# cirq_lcd.net
KiCad netlist of a schematic drawn in Altium Designer
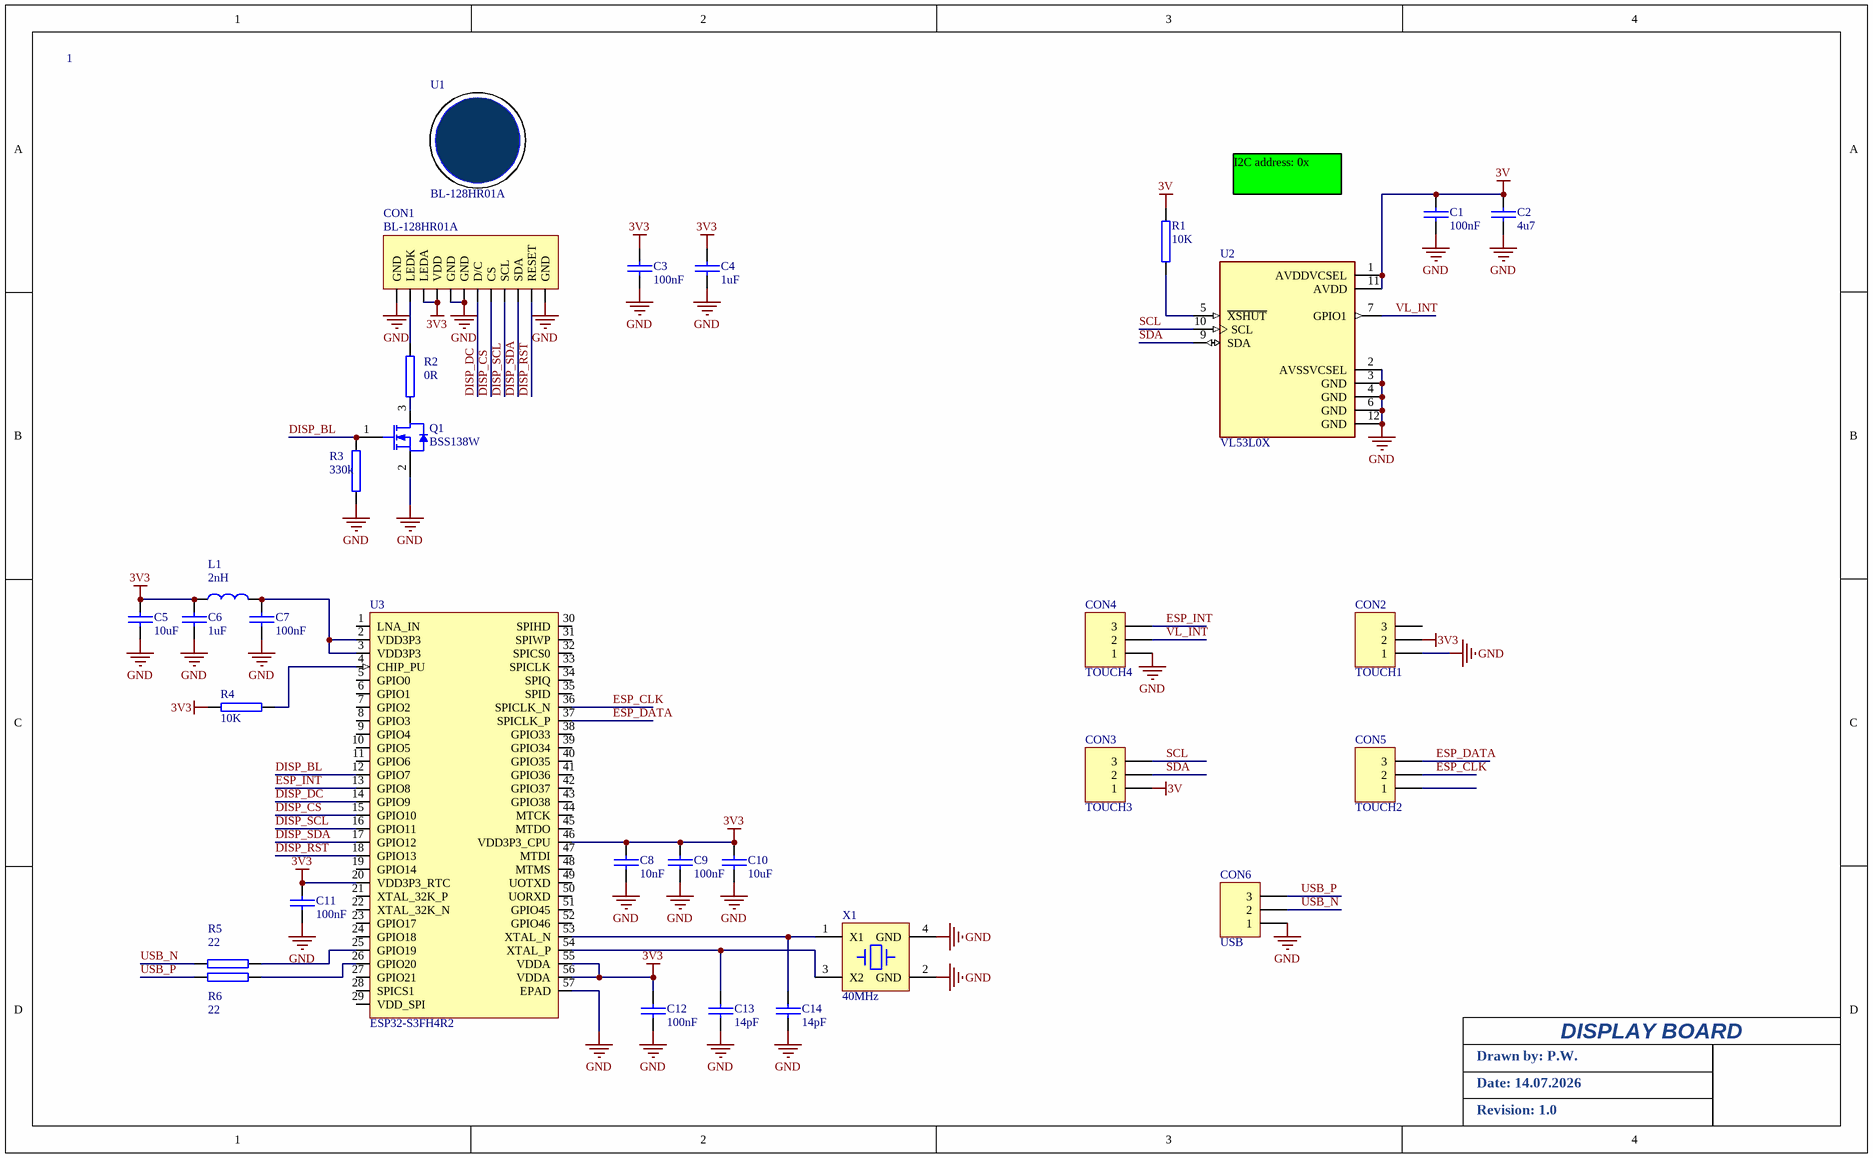
[diagram p0: cirq_lcd.SchDoc]

(export (version "E")
  (design (tool "Eeschema 10.0.6"))
  (components
    (comp (ref "1") (value "~") (footprint "NEWLOGO2") (libsource (lib "LIB_PW") (part "LOGO")))
    (comp (ref "C1")
      (value "100nF")
      (footprint "C0603L")
      (description "Capacitor")
      (libsource (lib "LIB_PW") (part "CAP"))
    )
    (comp (ref "C2")
      (value "4u7")
      (footprint "C0603L")
      (description "Capacitor")
      (libsource (lib "LIB_PW") (part "CAP"))
    )
    (comp (ref "C3")
      (value "100nF")
      (footprint "C0603L")
      (description "Capacitor")
      (libsource (lib "LIB_PW") (part "CAP"))
    )
    (comp (ref "C4")
      (value "1uF")
      (footprint "C0603L")
      (description "Capacitor")
      (libsource (lib "LIB_PW") (part "CAP"))
    )
    (comp (ref "C5")
      (value "10uF")
      (footprint "C0603L")
      (description "Capacitor")
      (libsource (lib "LIB_PW") (part "CAP"))
    )
    (comp (ref "C6")
      (value "1uF")
      (footprint "C0603L")
      (description "Capacitor")
      (libsource (lib "LIB_PW") (part "CAP"))
    )
    (comp (ref "C7")
      (value "100nF")
      (footprint "C0603L")
      (description "Capacitor")
      (libsource (lib "LIB_PW") (part "CAP"))
    )
    (comp (ref "C8")
      (value "10nF")
      (footprint "C0603L")
      (description "Capacitor")
      (libsource (lib "LIB_PW") (part "CAP"))
    )
    (comp (ref "C9")
      (value "100nF")
      (footprint "C0603L")
      (description "Capacitor")
      (libsource (lib "LIB_PW") (part "CAP"))
    )
    (comp (ref "C10")
      (value "10uF")
      (footprint "C0603L")
      (description "Capacitor")
      (libsource (lib "LIB_PW") (part "CAP"))
    )
    (comp (ref "C11")
      (value "100nF")
      (footprint "C0603L")
      (description "Capacitor")
      (libsource (lib "LIB_PW") (part "CAP"))
    )
    (comp (ref "C12")
      (value "100nF")
      (footprint "C0603L")
      (description "Capacitor")
      (libsource (lib "LIB_PW") (part "CAP"))
    )
    (comp (ref "C13")
      (value "14pF")
      (footprint "C0603L")
      (description "Capacitor")
      (libsource (lib "LIB_PW") (part "CAP"))
    )
    (comp (ref "C14")
      (value "14pF")
      (footprint "C0603L")
      (description "Capacitor")
      (libsource (lib "LIB_PW") (part "CAP"))
    )
    (comp (ref "CON1")
      (value "BL-128HR01A")
      (footprint "ROUND_TFT_1_28_C")
      (description "1.28 COLOR TFT 240X240 CONNECTOR")
      (libsource (lib "LIB_PW") (part "ROUND_1_28_TFT_C"))
    )
    (comp (ref "CON2")
      (value "TOUCH1")
      (footprint "HDR1X3_2mm")
      (description "Header, 3-Pin")
      (fields (field (name "PUBLISHER") "Altium Limited"))
      (libsource (lib "LIB_PW") (part "Header 3"))
    )
    (comp (ref "CON3")
      (value "TOUCH3")
      (footprint "HDR1X3_2mm")
      (description "Header, 3-Pin")
      (fields (field (name "PUBLISHER") "Altium Limited"))
      (libsource (lib "LIB_PW") (part "Header 3"))
    )
    (comp (ref "CON4")
      (value "TOUCH4")
      (footprint "HDR1X3_2mm")
      (description "Header, 3-Pin")
      (fields (field (name "PUBLISHER") "Altium Limited"))
      (libsource (lib "LIB_PW") (part "Header 3"))
    )
    (comp (ref "CON5")
      (value "TOUCH2")
      (footprint "HDR1X3_2mm")
      (description "Header, 3-Pin")
      (fields (field (name "PUBLISHER") "Altium Limited"))
      (libsource (lib "LIB_PW") (part "Header 3"))
    )
    (comp (ref "CON6")
      (value "USB")
      (footprint "HDR1X3_1mm27")
      (description "Header, 3-Pin")
      (fields (field (name "PUBLISHER") "Altium Limited"))
      (libsource (lib "LIB_PW") (part "Header 3"))
    )
    (comp (ref "L1") (value "2nH") (footprint "L0603") (libsource (lib "LIB_PW") (part "INDUCTOR")))
    (comp (ref "Q1")
      (value "BSS138W")
      (footprint "SOT-323")
      (description "N-MOSFET")
      (libsource (lib "LIB_PW") (part "BSS138W"))
    )
    (comp (ref "R1") (value "10K") (footprint "1608[0603]") (libsource (lib "LIB_PW") (part "RES")))
    (comp (ref "R2") (value "0R") (footprint "1608[0603]") (libsource (lib "LIB_PW") (part "RES")))
    (comp (ref "R3") (value "330k") (footprint "1608[0603]") (libsource (lib "LIB_PW") (part "RES")))
    (comp (ref "R4") (value "10K") (footprint "1608[0603]") (libsource (lib "LIB_PW") (part "RES")))
    (comp (ref "R5") (value "22") (footprint "1608[0603]") (libsource (lib "LIB_PW") (part "RES")))
    (comp (ref "R6") (value "22") (footprint "1608[0603]") (libsource (lib "LIB_PW") (part "RES")))
    (comp (ref "U1")
      (value "BL-128HR01A")
      (footprint "ROUND_TFT_1_28_S")
      (description "1.28 COLOR TFT 240X240 SCREEN")
      (libsource (lib "LIB_PW") (part "ROUND_1_28_TFT_S"))
    )
    (comp (ref "U2")
      (value "VL53L0X")
      (footprint "SENSOR_VL53L0X")
      (description "VL53L0X - Light, 3D Time-of-Flight _ToF_ Sensor Evaluation Board")
      (fields (field (name "MF") "STMicroelectronics"))
      (libsource (lib "LIB_PW") (part "VL53L0X"))
    )
    (comp (ref "U3")
      (value "ESP32-S3FH4R2")
      (footprint "QFN56_ESP32_7X7_EXP")
      (description "Bluetooth, WiFi 802.11b/g/n, Bluetooth v5.0 Transceiver Module 2.4GHz PCB Trace Surface Mount")
      (fields
        (field (name "MANUFACTURER") "Espressif Systems")
        (field (name "MANUFACTURER PART NUMBER") "ESP32-S3")
      )
      (libsource (lib "LIB_PW") (part "ESP32-S3"))
    )
    (comp (ref "X1")
      (value "40MHz")
      (footprint "X3x2")
      (description "TX3")
      (libsource (lib "LIB_PW") (part "CRYSTAL3"))
    )
  )
  (nets
    (net (code "1") (name "/DISP_BL") (class "Default")
      (node (ref "Q1") (pin "1") (pinfunction "G_1") (pintype "passive"))
      (node (ref "R3") (pin "2") (pinfunction "2_2") (pintype "passive"))
      (node (ref "U3") (pin "12") (pinfunction "GPIO7_12") (pintype "bidirectional"))
    )
    (net (code "2") (name "/DISP_CS") (class "Default")
      (node (ref "CON1") (pin "8") (pinfunction "CS_8") (pintype "passive"))
      (node (ref "U3") (pin "15") (pinfunction "GPIO10_15") (pintype "bidirectional"))
    )
    (net (code "3") (name "/DISP_DC") (class "Default")
      (node (ref "CON1") (pin "7") (pinfunction "D/C_7") (pintype "passive"))
      (node (ref "U3") (pin "14") (pinfunction "GPIO9_14") (pintype "bidirectional"))
    )
    (net (code "4") (name "/DISP_RST") (class "Default")
      (node (ref "CON1") (pin "11") (pinfunction "RESET_11") (pintype "passive"))
      (node (ref "U3") (pin "18") (pinfunction "GPIO13_18") (pintype "bidirectional"))
    )
    (net (code "5") (name "/DISP_SCL") (class "Default")
      (node (ref "CON1") (pin "9") (pinfunction "SCL_9") (pintype "passive"))
      (node (ref "U3") (pin "16") (pinfunction "GPIO11_16") (pintype "bidirectional"))
    )
    (net (code "6") (name "/DISP_SDA") (class "Default")
      (node (ref "CON1") (pin "10") (pinfunction "SDA_10") (pintype "passive"))
      (node (ref "U3") (pin "17") (pinfunction "GPIO12_17") (pintype "bidirectional"))
    )
    (net (code "7") (name "/ESP_CLK") (class "Default")
      (node (ref "CON5") (pin "2") (pinfunction "2_2") (pintype "passive"))
      (node (ref "U3") (pin "36") (pinfunction "SPICLK_N_36") (pintype "bidirectional"))
    )
    (net (code "8") (name "/ESP_DATA") (class "Default")
      (node (ref "CON5") (pin "3") (pinfunction "3_3") (pintype "passive"))
      (node (ref "U3") (pin "37") (pinfunction "SPICLK_P_37") (pintype "bidirectional"))
    )
    (net (code "9") (name "/ESP_INT") (class "Default")
      (node (ref "CON4") (pin "3") (pinfunction "3_3") (pintype "passive"))
      (node (ref "U3") (pin "13") (pinfunction "GPIO8_13") (pintype "bidirectional"))
    )
    (net (code "10") (name "/SCL") (class "Default")
      (node (ref "CON3") (pin "3") (pinfunction "3_3") (pintype "passive"))
      (node (ref "U2") (pin "10") (pinfunction "SCL_10") (pintype "input"))
    )
    (net (code "11") (name "/SDA") (class "Default")
      (node (ref "CON3") (pin "2") (pinfunction "2_2") (pintype "passive"))
      (node (ref "U2") (pin "9") (pinfunction "SDA_9") (pintype "bidirectional"))
    )
    (net (code "12") (name "/USB_N") (class "Default")
      (node (ref "CON6") (pin "2") (pinfunction "2_2") (pintype "passive"))
      (node (ref "R5") (pin "1") (pinfunction "1_1") (pintype "passive"))
    )
    (net (code "13") (name "/USB_P") (class "Default")
      (node (ref "CON6") (pin "3") (pinfunction "3_3") (pintype "passive"))
      (node (ref "R6") (pin "1") (pinfunction "1_1") (pintype "passive"))
    )
    (net (code "14") (name "/VL_INT") (class "Default")
      (node (ref "CON4") (pin "2") (pinfunction "2_2") (pintype "passive"))
      (node (ref "U2") (pin "7") (pinfunction "GPIO1_7") (pintype "output"))
    )
    (net (code "15") (name "3V") (class "Default")
      (node (ref "C1") (pin "1") (pinfunction "1_1") (pintype "passive"))
      (node (ref "C2") (pin "1") (pinfunction "1_1") (pintype "passive"))
      (node (ref "CON3") (pin "1") (pinfunction "1_1") (pintype "passive"))
      (node (ref "R1") (pin "2") (pinfunction "2_2") (pintype "passive"))
      (node (ref "U2") (pin "1") (pinfunction "AVDDVCSEL_1") (pintype "power_in"))
      (node (ref "U2") (pin "11") (pinfunction "AVDD_11") (pintype "power_in"))
    )
    (net (code "16") (name "3V3") (class "Default")
      (node (ref "C10") (pin "1") (pinfunction "1_1") (pintype "passive"))
      (node (ref "C11") (pin "1") (pinfunction "1_1") (pintype "passive"))
      (node (ref "C12") (pin "1") (pinfunction "1_1") (pintype "passive"))
      (node (ref "C3") (pin "1") (pinfunction "1_1") (pintype "passive"))
      (node (ref "C4") (pin "1") (pinfunction "1_1") (pintype "passive"))
      (node (ref "C5") (pin "1") (pinfunction "1_1") (pintype "passive"))
      (node (ref "C6") (pin "1") (pinfunction "1_1") (pintype "passive"))
      (node (ref "C8") (pin "1") (pinfunction "1_1") (pintype "passive"))
      (node (ref "C9") (pin "1") (pinfunction "1_1") (pintype "passive"))
      (node (ref "CON1") (pin "3") (pinfunction "LEDA_3") (pintype "passive"))
      (node (ref "CON1") (pin "4") (pinfunction "VDD_4") (pintype "passive"))
      (node (ref "CON2") (pin "2") (pinfunction "2_2") (pintype "passive"))
      (node (ref "L1") (pin "1") (pinfunction "1_1") (pintype "passive"))
      (node (ref "R4") (pin "2") (pinfunction "2_2") (pintype "passive"))
      (node (ref "U3") (pin "20") (pinfunction "VDD3P3_RTC_20") (pintype "power_in"))
      (node (ref "U3") (pin "46") (pinfunction "VDD3P3_CPU_46") (pintype "power_in"))
      (node (ref "U3") (pin "55") (pinfunction "VDDA_55") (pintype "power_in"))
      (node (ref "U3") (pin "56") (pinfunction "VDDA_56") (pintype "power_in"))
    )
    (net (code "17") (name "GND") (class "Default")
      (node (ref "C1") (pin "2") (pinfunction "2_2") (pintype "passive"))
      (node (ref "C10") (pin "2") (pinfunction "2_2") (pintype "passive"))
      (node (ref "C11") (pin "2") (pinfunction "2_2") (pintype "passive"))
      (node (ref "C12") (pin "2") (pinfunction "2_2") (pintype "passive"))
      (node (ref "C13") (pin "2") (pinfunction "2_2") (pintype "passive"))
      (node (ref "C14") (pin "1") (pinfunction "1_1") (pintype "passive"))
      (node (ref "C2") (pin "2") (pinfunction "2_2") (pintype "passive"))
      (node (ref "C3") (pin "2") (pinfunction "2_2") (pintype "passive"))
      (node (ref "C4") (pin "2") (pinfunction "2_2") (pintype "passive"))
      (node (ref "C5") (pin "2") (pinfunction "2_2") (pintype "passive"))
      (node (ref "C6") (pin "2") (pinfunction "2_2") (pintype "passive"))
      (node (ref "C7") (pin "2") (pinfunction "2_2") (pintype "passive"))
      (node (ref "C8") (pin "2") (pinfunction "2_2") (pintype "passive"))
      (node (ref "C9") (pin "2") (pinfunction "2_2") (pintype "passive"))
      (node (ref "CON1") (pin "1") (pinfunction "GND_1") (pintype "passive"))
      (node (ref "CON1") (pin "12") (pinfunction "GND_12") (pintype "passive"))
      (node (ref "CON1") (pin "5") (pinfunction "GND_5") (pintype "passive"))
      (node (ref "CON1") (pin "6") (pinfunction "GND_6") (pintype "passive"))
      (node (ref "CON2") (pin "1") (pinfunction "1_1") (pintype "passive"))
      (node (ref "CON4") (pin "1") (pinfunction "1_1") (pintype "passive"))
      (node (ref "CON6") (pin "1") (pinfunction "1_1") (pintype "passive"))
      (node (ref "Q1") (pin "2") (pinfunction "S_2") (pintype "passive"))
      (node (ref "R3") (pin "1") (pinfunction "1_1") (pintype "passive"))
      (node (ref "U2") (pin "12") (pinfunction "GND_12") (pintype "power_in"))
      (node (ref "U2") (pin "2") (pinfunction "AVSSVCSEL_2") (pintype "power_in"))
      (node (ref "U2") (pin "3") (pinfunction "GND_3") (pintype "power_in"))
      (node (ref "U2") (pin "4") (pinfunction "GND_4") (pintype "power_in"))
      (node (ref "U2") (pin "6") (pinfunction "GND_6") (pintype "power_in"))
      (node (ref "U3") (pin "57") (pinfunction "EPAD_57") (pintype "power_in"))
      (node (ref "X1") (pin "2") (pinfunction "GND_2") (pintype "passive"))
      (node (ref "X1") (pin "4") (pinfunction "GND_4") (pintype "passive"))
    )
    (net (code "18") (name "Net-(C7-Pad1)") (class "Default")
      (node (ref "C7") (pin "1") (pinfunction "1_1") (pintype "passive"))
      (node (ref "L1") (pin "2") (pinfunction "2_2") (pintype "passive"))
      (node (ref "U3") (pin "2") (pinfunction "VDD3P3_2") (pintype "power_in"))
      (node (ref "U3") (pin "3") (pinfunction "VDD3P3_3") (pintype "power_in"))
    )
    (net (code "19") (name "Net-(CON1-LEDK)") (class "Default")
      (node (ref "CON1") (pin "2") (pinfunction "LEDK_2") (pintype "passive"))
      (node (ref "R2") (pin "2") (pinfunction "2_2") (pintype "passive"))
    )
    (net (code "20") (name "Net-(Q1-D)") (class "Default")
      (node (ref "Q1") (pin "3") (pinfunction "D_3") (pintype "passive"))
      (node (ref "R2") (pin "1") (pinfunction "1_1") (pintype "passive"))
    )
    (net (code "21") (name "Net-(U2-~{XSHUT})") (class "Default")
      (node (ref "R1") (pin "1") (pinfunction "1_1") (pintype "passive"))
      (node (ref "U2") (pin "5") (pinfunction "~{XSHUT}_5") (pintype "input"))
    )
    (net (code "22") (name "Net-(U3-CHIP_PU)") (class "Default")
      (node (ref "R4") (pin "1") (pinfunction "1_1") (pintype "passive"))
      (node (ref "U3") (pin "4") (pinfunction "CHIP_PU_4") (pintype "input"))
    )
    (net (code "23") (name "Net-(U3-GPIO19)") (class "Default")
      (node (ref "R5") (pin "2") (pinfunction "2_2") (pintype "passive"))
      (node (ref "U3") (pin "25") (pinfunction "GPIO19_25") (pintype "bidirectional"))
    )
    (net (code "24") (name "Net-(U3-GPIO20)") (class "Default")
      (node (ref "R6") (pin "2") (pinfunction "2_2") (pintype "passive"))
      (node (ref "U3") (pin "26") (pinfunction "GPIO20_26") (pintype "bidirectional"))
    )
    (net (code "25") (name "Net-(U3-XTAL_N)") (class "Default")
      (node (ref "C14") (pin "2") (pinfunction "2_2") (pintype "passive"))
      (node (ref "U3") (pin "53") (pinfunction "XTAL_N_53") (pintype "passive"))
      (node (ref "X1") (pin "1") (pinfunction "X1_1") (pintype "passive"))
    )
    (net (code "26") (name "Net-(U3-XTAL_P)") (class "Default")
      (node (ref "C13") (pin "1") (pinfunction "1_1") (pintype "passive"))
      (node (ref "U3") (pin "54") (pinfunction "XTAL_P_54") (pintype "passive"))
      (node (ref "X1") (pin "3") (pinfunction "X2_3") (pintype "passive"))
    )
    (net (code "27") (name "unconnected-(CON2-Pad3)") (class "Default")
      (node (ref "CON2") (pin "3") (pinfunction "3_3") (pintype "passive"))
    )
    (net (code "28") (name "unconnected-(CON5-Pad1)") (class "Default")
      (node (ref "CON5") (pin "1") (pinfunction "1_1") (pintype "passive"))
    )
    (net (code "29") (name "unconnected-(U3-GPIO0-Pad5)") (class "Default")
      (node (ref "U3") (pin "5") (pinfunction "GPIO0_5") (pintype "bidirectional"))
    )
    (net (code "30") (name "unconnected-(U3-GPIO1-Pad6)") (class "Default")
      (node (ref "U3") (pin "6") (pinfunction "GPIO1_6") (pintype "bidirectional"))
    )
    (net (code "31") (name "unconnected-(U3-GPIO2-Pad7)") (class "Default")
      (node (ref "U3") (pin "7") (pinfunction "GPIO2_7") (pintype "bidirectional"))
    )
    (net (code "32") (name "unconnected-(U3-GPIO3-Pad8)") (class "Default")
      (node (ref "U3") (pin "8") (pinfunction "GPIO3_8") (pintype "bidirectional"))
    )
    (net (code "33") (name "unconnected-(U3-GPIO4-Pad9)") (class "Default")
      (node (ref "U3") (pin "9") (pinfunction "GPIO4_9") (pintype "bidirectional"))
    )
    (net (code "34") (name "unconnected-(U3-GPIO5-Pad10)") (class "Default")
      (node (ref "U3") (pin "10") (pinfunction "GPIO5_10") (pintype "bidirectional"))
    )
    (net (code "35") (name "unconnected-(U3-GPIO6-Pad11)") (class "Default")
      (node (ref "U3") (pin "11") (pinfunction "GPIO6_11") (pintype "bidirectional"))
    )
    (net (code "36") (name "unconnected-(U3-GPIO14-Pad19)") (class "Default")
      (node (ref "U3") (pin "19") (pinfunction "GPIO14_19") (pintype "bidirectional"))
    )
    (net (code "37") (name "unconnected-(U3-GPIO17-Pad23)") (class "Default")
      (node (ref "U3") (pin "23") (pinfunction "GPIO17_23") (pintype "bidirectional"))
    )
    (net (code "38") (name "unconnected-(U3-GPIO18-Pad24)") (class "Default")
      (node (ref "U3") (pin "24") (pinfunction "GPIO18_24") (pintype "bidirectional"))
    )
    (net (code "39") (name "unconnected-(U3-GPIO21-Pad27)") (class "Default")
      (node (ref "U3") (pin "27") (pinfunction "GPIO21_27") (pintype "bidirectional"))
    )
    (net (code "40") (name "unconnected-(U3-GPIO33-Pad38)") (class "Default")
      (node (ref "U3") (pin "38") (pinfunction "GPIO33_38") (pintype "bidirectional"))
    )
    (net (code "41") (name "unconnected-(U3-GPIO34-Pad39)") (class "Default")
      (node (ref "U3") (pin "39") (pinfunction "GPIO34_39") (pintype "bidirectional"))
    )
    (net (code "42") (name "unconnected-(U3-GPIO35-Pad40)") (class "Default")
      (node (ref "U3") (pin "40") (pinfunction "GPIO35_40") (pintype "bidirectional"))
    )
    (net (code "43") (name "unconnected-(U3-GPIO36-Pad41)") (class "Default")
      (node (ref "U3") (pin "41") (pinfunction "GPIO36_41") (pintype "bidirectional"))
    )
    (net (code "44") (name "unconnected-(U3-GPIO37-Pad42)") (class "Default")
      (node (ref "U3") (pin "42") (pinfunction "GPIO37_42") (pintype "bidirectional"))
    )
    (net (code "45") (name "unconnected-(U3-GPIO38-Pad43)") (class "Default")
      (node (ref "U3") (pin "43") (pinfunction "GPIO38_43") (pintype "bidirectional"))
    )
    (net (code "46") (name "unconnected-(U3-GPIO45-Pad51)") (class "Default")
      (node (ref "U3") (pin "51") (pinfunction "GPIO45_51") (pintype "bidirectional"))
    )
    (net (code "47") (name "unconnected-(U3-GPIO46-Pad52)") (class "Default")
      (node (ref "U3") (pin "52") (pinfunction "GPIO46_52") (pintype "bidirectional"))
    )
    (net (code "48") (name "unconnected-(U3-LNA_IN-Pad1)") (class "Default")
      (node (ref "U3") (pin "1") (pinfunction "LNA_IN_1") (pintype "bidirectional"))
    )
    (net (code "49") (name "unconnected-(U3-MTCK-Pad44)") (class "Default")
      (node (ref "U3") (pin "44") (pinfunction "MTCK_44") (pintype "bidirectional"))
    )
    (net (code "50") (name "unconnected-(U3-MTDI-Pad47)") (class "Default")
      (node (ref "U3") (pin "47") (pinfunction "MTDI_47") (pintype "bidirectional"))
    )
    (net (code "51") (name "unconnected-(U3-MTDO-Pad45)") (class "Default")
      (node (ref "U3") (pin "45") (pinfunction "MTDO_45") (pintype "bidirectional"))
    )
    (net (code "52") (name "unconnected-(U3-MTMS-Pad48)") (class "Default")
      (node (ref "U3") (pin "48") (pinfunction "MTMS_48") (pintype "bidirectional"))
    )
    (net (code "53") (name "unconnected-(U3-SPICLK-Pad33)") (class "Default")
      (node (ref "U3") (pin "33") (pinfunction "SPICLK_33") (pintype "bidirectional"))
    )
    (net (code "54") (name "unconnected-(U3-SPICS0-Pad32)") (class "Default")
      (node (ref "U3") (pin "32") (pinfunction "SPICS0_32") (pintype "bidirectional"))
    )
    (net (code "55") (name "unconnected-(U3-SPICS1-Pad28)") (class "Default")
      (node (ref "U3") (pin "28") (pinfunction "SPICS1_28") (pintype "bidirectional"))
    )
    (net (code "56") (name "unconnected-(U3-SPID-Pad35)") (class "Default")
      (node (ref "U3") (pin "35") (pinfunction "SPID_35") (pintype "bidirectional"))
    )
    (net (code "57") (name "unconnected-(U3-SPIHD-Pad30)") (class "Default")
      (node (ref "U3") (pin "30") (pinfunction "SPIHD_30") (pintype "bidirectional"))
    )
    (net (code "58") (name "unconnected-(U3-SPIQ-Pad34)") (class "Default")
      (node (ref "U3") (pin "34") (pinfunction "SPIQ_34") (pintype "bidirectional"))
    )
    (net (code "59") (name "unconnected-(U3-SPIWP-Pad31)") (class "Default")
      (node (ref "U3") (pin "31") (pinfunction "SPIWP_31") (pintype "bidirectional"))
    )
    (net (code "60") (name "unconnected-(U3-UORXD-Pad50)") (class "Default")
      (node (ref "U3") (pin "50") (pinfunction "UORXD_50") (pintype "bidirectional"))
    )
    (net (code "61") (name "unconnected-(U3-UOTXD-Pad49)") (class "Default")
      (node (ref "U3") (pin "49") (pinfunction "UOTXD_49") (pintype "bidirectional"))
    )
    (net (code "62") (name "unconnected-(U3-VDD_SPI-Pad29)") (class "Default")
      (node (ref "U3") (pin "29") (pinfunction "VDD_SPI_29") (pintype "power_in"))
    )
    (net (code "63") (name "unconnected-(U3-XTAL_32K_N-Pad22)") (class "Default")
      (node (ref "U3") (pin "22") (pinfunction "XTAL_32K_N_22") (pintype "passive"))
    )
    (net (code "64") (name "unconnected-(U3-XTAL_32K_P-Pad21)") (class "Default")
      (node (ref "U3") (pin "21") (pinfunction "XTAL_32K_P_21") (pintype "passive"))
    )
  )
)
